# Microcontroller.net
KiCad netlist of a schematic drawn in Altium Designer
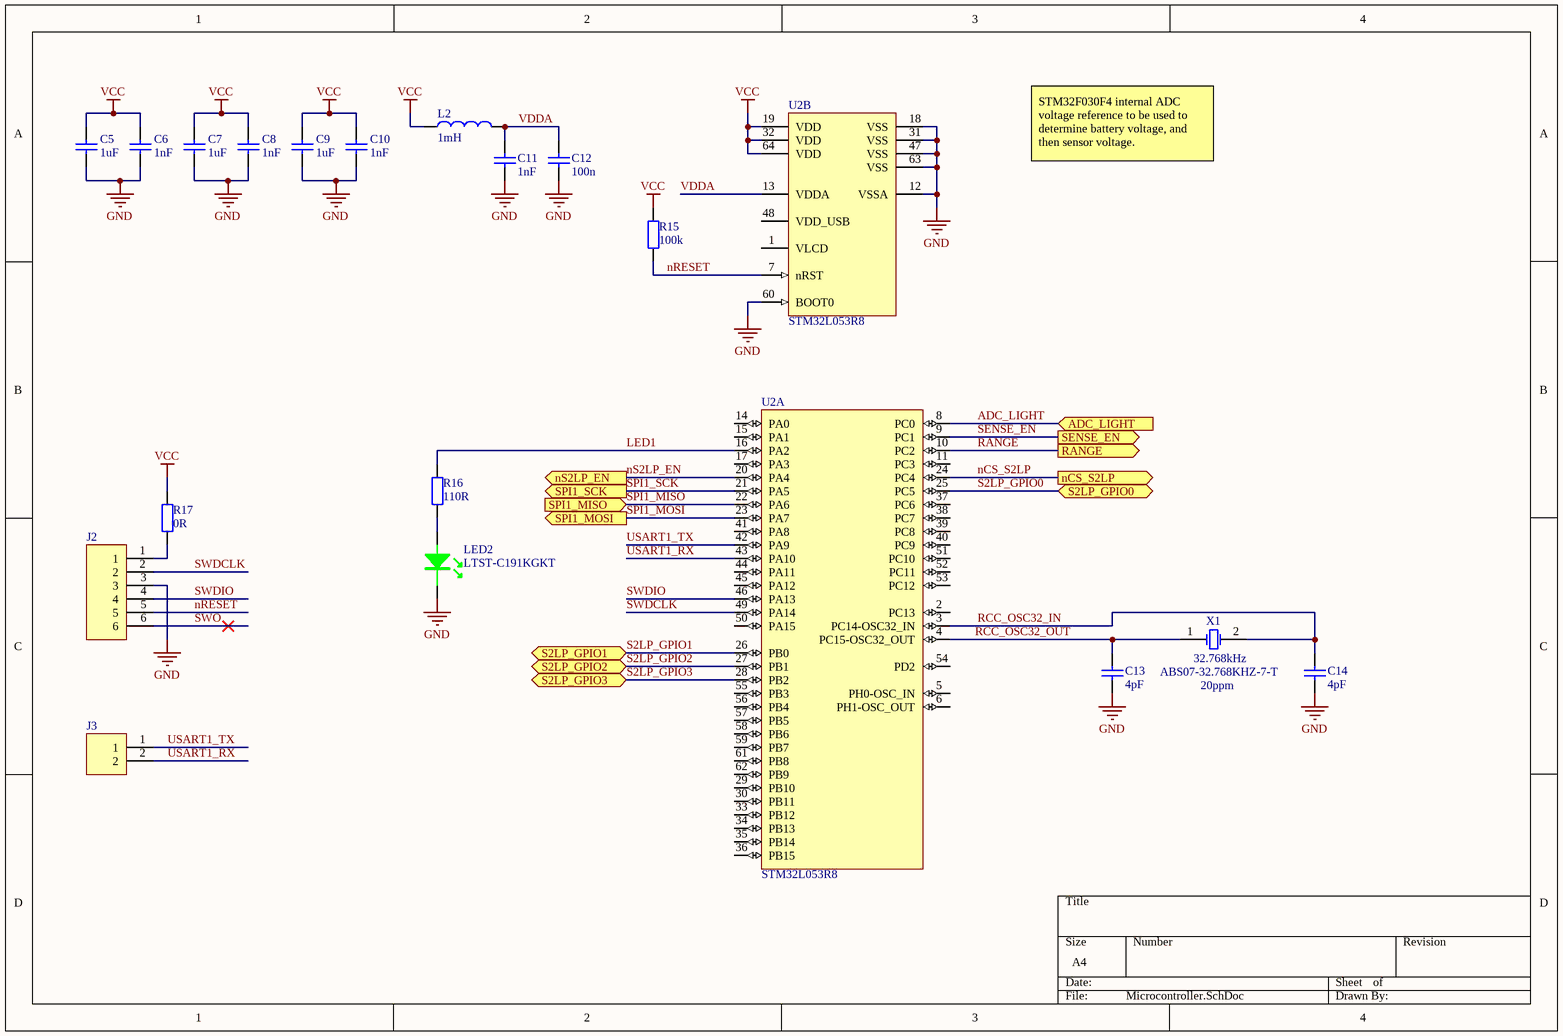
[diagram p0: Microcontroller.SchDoc]

(export (version "E")
  (design (tool "Eeschema 10.0.6"))
  (components
    (comp (ref "C5")
      (value "~")
      (footprint "C0603")
      (description "CAP")
      (fields
        (field (name "MANUFACTURER") "Yageo")
        (field (name "MANUFACTURER PART NUMBER") "CC0603KRX7R9BB105")
        (field (name "CAPACITANCE") "1uF")
      )
      (libsource (lib "Light Sensor Node") (part "CAP"))
    )
    (comp (ref "C6")
      (value "1nF")
      (footprint "C0603")
      (description "CAP")
      (fields
        (field (name "MANUFACTURER") "Yageo")
        (field (name "MANUFACTURER PART NUMBER") "CC0603KRX7R9BB102")
      )
      (libsource (lib "Light Sensor Node") (part "CAP"))
    )
    (comp (ref "C7")
      (value "~")
      (footprint "C0603")
      (description "CAP")
      (fields
        (field (name "MANUFACTURER") "Yageo")
        (field (name "MANUFACTURER PART NUMBER") "CC0603KRX7R9BB105")
        (field (name "CAPACITANCE") "1uF")
      )
      (libsource (lib "Light Sensor Node") (part "CAP"))
    )
    (comp (ref "C8")
      (value "1nF")
      (footprint "C0603")
      (description "CAP")
      (fields
        (field (name "MANUFACTURER") "Yageo")
        (field (name "MANUFACTURER PART NUMBER") "CC0603KRX7R9BB102")
      )
      (libsource (lib "Light Sensor Node") (part "CAP"))
    )
    (comp (ref "C9")
      (value "~")
      (footprint "C0603")
      (description "CAP")
      (fields
        (field (name "MANUFACTURER") "Yageo")
        (field (name "MANUFACTURER PART NUMBER") "CC0603KRX7R9BB105")
        (field (name "CAPACITANCE") "1uF")
      )
      (libsource (lib "Light Sensor Node") (part "CAP"))
    )
    (comp (ref "C10")
      (value "1nF")
      (footprint "C0603")
      (description "CAP")
      (fields
        (field (name "MANUFACTURER") "Yageo")
        (field (name "MANUFACTURER PART NUMBER") "CC0603KRX7R9BB102")
      )
      (libsource (lib "Light Sensor Node") (part "CAP"))
    )
    (comp (ref "C11")
      (value "1nF")
      (footprint "C0603")
      (description "CAP")
      (fields
        (field (name "MANUFACTURER") "Yageo")
        (field (name "MANUFACTURER PART NUMBER") "CC0603KRX7R9BB102")
      )
      (libsource (lib "Light Sensor Node") (part "CAP"))
    )
    (comp (ref "C12")
      (value "100n")
      (footprint "C0603")
      (description "CAP")
      (fields
        (field (name "MANUFACTURER") "Yageo")
        (field (name "MANUFACTURER PART NUMBER") "CC0603ZRY5V9BB104")
      )
      (libsource (lib "Light Sensor Node") (part "CAP"))
    )
    (comp (ref "C13")
      (value "4pF")
      (footprint "C0603")
      (description "CAP")
      (fields
        (field (name "MANUFACTURER") "Yageo")
        (field (name "MANUFACTURER PART NUMBER") "CC0603CRNPO9BN4R0")
      )
      (libsource (lib "Light Sensor Node") (part "CAP"))
    )
    (comp (ref "C14")
      (value "4pF")
      (footprint "C0603")
      (description "CAP")
      (fields
        (field (name "MANUFACTURER") "Yageo")
        (field (name "MANUFACTURER PART NUMBER") "CC0603CRNPO9BN4R0")
      )
      (libsource (lib "Light Sensor Node") (part "CAP"))
    )
    (comp (ref "J2")
      (value "~")
      (footprint "HEADER_6WAY")
      (libsource (lib "Light Sensor Node") (part "6WAY"))
    )
    (comp (ref "J3")
      (value "~")
      (footprint "HEADER_2WAY")
      (libsource (lib "Light Sensor Node") (part "2WAY"))
    )
    (comp (ref "L2")
      (value "IND")
      (footprint "TAIYOYUDEN_CB2518T102K")
      (fields
        (field (name "MANUFACTURER") "Taiyo Yuden")
        (field (name "MANUFACTURER PART NUMBER") "CB2518T102K")
        (field (name "INDUCTANCE") "1mH")
      )
      (libsource (lib "Light Sensor Node") (part "IND"))
    )
    (comp (ref "LED2")
      (value "LTST-C191KGKT")
      (footprint "LITEON_LTST-C191KGKT")
      (fields (field (name "MANUFACTURER") "Lite On"))
      (libsource (lib "Light Sensor Node") (part "LED_Green"))
    )
    (comp (ref "R15")
      (value "100k")
      (footprint "R0603")
      (description "RES")
      (fields (field (name "TOLERANCE") "1%") (field (name "MANUFACTURER") "Yageo"))
      (libsource (lib "") (part "RES_1"))
    )
    (comp (ref "R16")
      (value "110R")
      (footprint "R0603")
      (description "RES")
      (fields
        (field (name "MANUFACTURER") "Yageo")
        (field (name "MANUFACTURER PART NUMBER") "RC0603FR-07110RL")
      )
      (libsource (lib "") (part "RES_1"))
    )
    (comp (ref "R17")
      (value "0R")
      (footprint "R0603")
      (description "RES")
      (fields
        (field (name "MANUFACTURER") "Yageo")
        (field (name "MANUFACTURER PART NUMBER") "RC0603JR-070RL")
      )
      (libsource (lib "Light Sensor Node") (part "RES"))
    )
    (comp (ref "U2")
      (value "STM32L053R8")
      (footprint "ST_STM32L053R8Tx")
      (fields (field (name "MANUFACTURER") "ST"))
      (libsource (lib "Light Sensor Node") (part "STM32L053R8"))
    )
    (comp (ref "X1")
      (value "32.768kHz")
      (footprint "Abracon_ABS07")
      (description "Crystal Oscillator")
      (fields
        (field (name "MANUFACTURER") "Abracon")
        (field (name "MANUFACTURER PART NUMBER") "ABS07-32.768KHZ-7-T")
        (field (name "FREQUENCY TOLERANCE") "20ppm")
      )
      (libsource (lib "Light Sensor Node") (part "ABRACON_ABS07"))
    )
  )
  (nets
    (net (code "1") (name "/ADC_LIGHT") (class "Default")
      (node (ref "U2") (pin "8") (pinfunction "PC0_8") (pintype "bidirectional"))
    )
    (net (code "2") (name "/LED1") (class "Default")
      (node (ref "R16") (pin "1") (pinfunction "1_1") (pintype "passive"))
      (node (ref "U2") (pin "16") (pinfunction "PA2_16") (pintype "bidirectional"))
    )
    (net (code "3") (name "/RANGE") (class "Default")
      (node (ref "U2") (pin "10") (pinfunction "PC2_10") (pintype "bidirectional"))
    )
    (net (code "4") (name "/RCC_OSC32_IN") (class "Default")
      (node (ref "C14") (pin "2") (pinfunction "2_2") (pintype "passive"))
      (node (ref "U2") (pin "3") (pinfunction "PC14-OSC32_IN_3") (pintype "bidirectional"))
      (node (ref "X1") (pin "2") (pinfunction "OSC2_2") (pintype "passive"))
    )
    (net (code "5") (name "/RCC_OSC32_OUT") (class "Default")
      (node (ref "C13") (pin "2") (pinfunction "2_2") (pintype "passive"))
      (node (ref "U2") (pin "4") (pinfunction "PC15-OSC32_OUT_4") (pintype "bidirectional"))
      (node (ref "X1") (pin "1") (pinfunction "OSC1_1") (pintype "passive"))
    )
    (net (code "6") (name "/S2LP_GPIO0") (class "Default")
      (node (ref "U2") (pin "25") (pinfunction "PC5_25") (pintype "bidirectional"))
    )
    (net (code "7") (name "/S2LP_GPIO1") (class "Default")
      (node (ref "U2") (pin "26") (pinfunction "PB0_26") (pintype "bidirectional"))
    )
    (net (code "8") (name "/S2LP_GPIO2") (class "Default")
      (node (ref "U2") (pin "27") (pinfunction "PB1_27") (pintype "bidirectional"))
    )
    (net (code "9") (name "/S2LP_GPIO3") (class "Default")
      (node (ref "U2") (pin "28") (pinfunction "PB2_28") (pintype "bidirectional"))
    )
    (net (code "10") (name "/SENSE_EN") (class "Default")
      (node (ref "U2") (pin "9") (pinfunction "PC1_9") (pintype "bidirectional"))
    )
    (net (code "11") (name "/SPI1_MISO") (class "Default")
      (node (ref "U2") (pin "22") (pinfunction "PA6_22") (pintype "bidirectional"))
    )
    (net (code "12") (name "/SPI1_MOSI") (class "Default")
      (node (ref "U2") (pin "23") (pinfunction "PA7_23") (pintype "bidirectional"))
    )
    (net (code "13") (name "/SPI1_SCK") (class "Default")
      (node (ref "U2") (pin "21") (pinfunction "PA5_21") (pintype "bidirectional"))
    )
    (net (code "14") (name "/SWDCLK") (class "Default")
      (node (ref "J2") (pin "2") (pinfunction "2_2") (pintype "passive"))
      (node (ref "U2") (pin "49") (pinfunction "PA14_49") (pintype "bidirectional"))
    )
    (net (code "15") (name "/SWDIO") (class "Default")
      (node (ref "J2") (pin "4") (pinfunction "4_4") (pintype "passive"))
      (node (ref "U2") (pin "46") (pinfunction "PA13_46") (pintype "bidirectional"))
    )
    (net (code "16") (name "/SWO") (class "Default")
      (node (ref "J2") (pin "6") (pinfunction "6_6") (pintype "passive"))
    )
    (net (code "17") (name "/USART1_RX") (class "Default")
      (node (ref "J3") (pin "2") (pinfunction "2_2") (pintype "passive"))
      (node (ref "U2") (pin "43") (pinfunction "PA10_43") (pintype "bidirectional"))
    )
    (net (code "18") (name "/USART1_TX") (class "Default")
      (node (ref "J3") (pin "1") (pinfunction "1_1") (pintype "passive"))
      (node (ref "U2") (pin "42") (pinfunction "PA9_42") (pintype "bidirectional"))
    )
    (net (code "19") (name "/VDDA") (class "Default")
      (node (ref "C11") (pin "1") (pinfunction "1_1") (pintype "passive"))
      (node (ref "C12") (pin "2") (pinfunction "2_2") (pintype "passive"))
      (node (ref "L2") (pin "1") (pinfunction "1_1") (pintype "passive"))
      (node (ref "U2") (pin "13") (pinfunction "VDDA_13") (pintype "power_in"))
    )
    (net (code "20") (name "/nCS_S2LP") (class "Default")
      (node (ref "U2") (pin "24") (pinfunction "PC4_24") (pintype "bidirectional"))
    )
    (net (code "21") (name "/nRESET") (class "Default")
      (node (ref "J2") (pin "5") (pinfunction "5_5") (pintype "passive"))
      (node (ref "R15") (pin "2") (pinfunction "2_2") (pintype "passive"))
      (node (ref "U2") (pin "7") (pinfunction "nRST_7") (pintype "input"))
    )
    (net (code "22") (name "/nS2LP_EN") (class "Default")
      (node (ref "U2") (pin "20") (pinfunction "PA4_20") (pintype "bidirectional"))
    )
    (net (code "23") (name "GND") (class "Default")
      (node (ref "C10") (pin "2") (pinfunction "2_2") (pintype "passive"))
      (node (ref "C11") (pin "2") (pinfunction "2_2") (pintype "passive"))
      (node (ref "C12") (pin "1") (pinfunction "1_1") (pintype "passive"))
      (node (ref "C13") (pin "1") (pinfunction "1_1") (pintype "passive"))
      (node (ref "C14") (pin "1") (pinfunction "1_1") (pintype "passive"))
      (node (ref "C5") (pin "1") (pinfunction "1_1") (pintype "passive"))
      (node (ref "C6") (pin "2") (pinfunction "2_2") (pintype "passive"))
      (node (ref "C7") (pin "1") (pinfunction "1_1") (pintype "passive"))
      (node (ref "C8") (pin "2") (pinfunction "2_2") (pintype "passive"))
      (node (ref "C9") (pin "1") (pinfunction "1_1") (pintype "passive"))
      (node (ref "J2") (pin "3") (pinfunction "3_3") (pintype "passive"))
      (node (ref "LED2") (pin "K") (pinfunction "K_K") (pintype "passive"))
      (node (ref "U2") (pin "12") (pinfunction "VSSA_12") (pintype "power_in"))
      (node (ref "U2") (pin "18") (pinfunction "VSS_18") (pintype "power_in"))
      (node (ref "U2") (pin "31") (pinfunction "VSS_31") (pintype "power_in"))
      (node (ref "U2") (pin "47") (pinfunction "VSS_47") (pintype "power_in"))
      (node (ref "U2") (pin "60") (pinfunction "BOOT0_60") (pintype "input"))
      (node (ref "U2") (pin "63") (pinfunction "VSS_63") (pintype "power_in"))
    )
    (net (code "24") (name "Net-(J2-Pad1)") (class "Default")
      (node (ref "J2") (pin "1") (pinfunction "1_1") (pintype "passive"))
      (node (ref "R17") (pin "1") (pinfunction "1_1") (pintype "passive"))
    )
    (net (code "25") (name "Net-(LED2-PadA)") (class "Default")
      (node (ref "LED2") (pin "A") (pinfunction "A_A") (pintype "passive"))
      (node (ref "R16") (pin "2") (pinfunction "2_2") (pintype "passive"))
    )
    (net (code "26") (name "VCC") (class "Default")
      (node (ref "C10") (pin "1") (pinfunction "1_1") (pintype "passive"))
      (node (ref "C5") (pin "2") (pinfunction "2_2") (pintype "passive"))
      (node (ref "C6") (pin "1") (pinfunction "1_1") (pintype "passive"))
      (node (ref "C7") (pin "2") (pinfunction "2_2") (pintype "passive"))
      (node (ref "C8") (pin "1") (pinfunction "1_1") (pintype "passive"))
      (node (ref "C9") (pin "2") (pinfunction "2_2") (pintype "passive"))
      (node (ref "L2") (pin "2") (pinfunction "2_2") (pintype "passive"))
      (node (ref "R15") (pin "1") (pinfunction "1_1") (pintype "passive"))
      (node (ref "R17") (pin "2") (pinfunction "2_2") (pintype "passive"))
      (node (ref "U2") (pin "19") (pinfunction "VDD_19") (pintype "power_in"))
      (node (ref "U2") (pin "32") (pinfunction "VDD_32") (pintype "power_in"))
      (node (ref "U2") (pin "64") (pinfunction "VDD_64") (pintype "power_in"))
    )
    (net (code "27") (name "unconnected-(U2A-PA0-Pad14)") (class "Default")
      (node (ref "U2") (pin "14") (pinfunction "PA0_14") (pintype "bidirectional"))
    )
    (net (code "28") (name "unconnected-(U2A-PA1-Pad15)") (class "Default")
      (node (ref "U2") (pin "15") (pinfunction "PA1_15") (pintype "bidirectional"))
    )
    (net (code "29") (name "unconnected-(U2A-PA3-Pad17)") (class "Default")
      (node (ref "U2") (pin "17") (pinfunction "PA3_17") (pintype "bidirectional"))
    )
    (net (code "30") (name "unconnected-(U2A-PA8-Pad41)") (class "Default")
      (node (ref "U2") (pin "41") (pinfunction "PA8_41") (pintype "bidirectional"))
    )
    (net (code "31") (name "unconnected-(U2A-PA11-Pad44)") (class "Default")
      (node (ref "U2") (pin "44") (pinfunction "PA11_44") (pintype "bidirectional"))
    )
    (net (code "32") (name "unconnected-(U2A-PA12-Pad45)") (class "Default")
      (node (ref "U2") (pin "45") (pinfunction "PA12_45") (pintype "bidirectional"))
    )
    (net (code "33") (name "unconnected-(U2A-PA15-Pad50)") (class "Default")
      (node (ref "U2") (pin "50") (pinfunction "PA15_50") (pintype "bidirectional"))
    )
    (net (code "34") (name "unconnected-(U2A-PB3-Pad55)") (class "Default")
      (node (ref "U2") (pin "55") (pinfunction "PB3_55") (pintype "bidirectional"))
    )
    (net (code "35") (name "unconnected-(U2A-PB4-Pad56)") (class "Default")
      (node (ref "U2") (pin "56") (pinfunction "PB4_56") (pintype "bidirectional"))
    )
    (net (code "36") (name "unconnected-(U2A-PB5-Pad57)") (class "Default")
      (node (ref "U2") (pin "57") (pinfunction "PB5_57") (pintype "bidirectional"))
    )
    (net (code "37") (name "unconnected-(U2A-PB6-Pad58)") (class "Default")
      (node (ref "U2") (pin "58") (pinfunction "PB6_58") (pintype "bidirectional"))
    )
    (net (code "38") (name "unconnected-(U2A-PB7-Pad59)") (class "Default")
      (node (ref "U2") (pin "59") (pinfunction "PB7_59") (pintype "bidirectional"))
    )
    (net (code "39") (name "unconnected-(U2A-PB8-Pad61)") (class "Default")
      (node (ref "U2") (pin "61") (pinfunction "PB8_61") (pintype "bidirectional"))
    )
    (net (code "40") (name "unconnected-(U2A-PB9-Pad62)") (class "Default")
      (node (ref "U2") (pin "62") (pinfunction "PB9_62") (pintype "bidirectional"))
    )
    (net (code "41") (name "unconnected-(U2A-PB10-Pad29)") (class "Default")
      (node (ref "U2") (pin "29") (pinfunction "PB10_29") (pintype "bidirectional"))
    )
    (net (code "42") (name "unconnected-(U2A-PB11-Pad30)") (class "Default")
      (node (ref "U2") (pin "30") (pinfunction "PB11_30") (pintype "bidirectional"))
    )
    (net (code "43") (name "unconnected-(U2A-PB12-Pad33)") (class "Default")
      (node (ref "U2") (pin "33") (pinfunction "PB12_33") (pintype "bidirectional"))
    )
    (net (code "44") (name "unconnected-(U2A-PB13-Pad34)") (class "Default")
      (node (ref "U2") (pin "34") (pinfunction "PB13_34") (pintype "bidirectional"))
    )
    (net (code "45") (name "unconnected-(U2A-PB14-Pad35)") (class "Default")
      (node (ref "U2") (pin "35") (pinfunction "PB14_35") (pintype "bidirectional"))
    )
    (net (code "46") (name "unconnected-(U2A-PB15-Pad36)") (class "Default")
      (node (ref "U2") (pin "36") (pinfunction "PB15_36") (pintype "bidirectional"))
    )
    (net (code "47") (name "unconnected-(U2A-PC3-Pad11)") (class "Default")
      (node (ref "U2") (pin "11") (pinfunction "PC3_11") (pintype "bidirectional"))
    )
    (net (code "48") (name "unconnected-(U2A-PC6-Pad37)") (class "Default")
      (node (ref "U2") (pin "37") (pinfunction "PC6_37") (pintype "bidirectional"))
    )
    (net (code "49") (name "unconnected-(U2A-PC7-Pad38)") (class "Default")
      (node (ref "U2") (pin "38") (pinfunction "PC7_38") (pintype "bidirectional"))
    )
    (net (code "50") (name "unconnected-(U2A-PC8-Pad39)") (class "Default")
      (node (ref "U2") (pin "39") (pinfunction "PC8_39") (pintype "bidirectional"))
    )
    (net (code "51") (name "unconnected-(U2A-PC9-Pad40)") (class "Default")
      (node (ref "U2") (pin "40") (pinfunction "PC9_40") (pintype "bidirectional"))
    )
    (net (code "52") (name "unconnected-(U2A-PC10-Pad51)") (class "Default")
      (node (ref "U2") (pin "51") (pinfunction "PC10_51") (pintype "bidirectional"))
    )
    (net (code "53") (name "unconnected-(U2A-PC11-Pad52)") (class "Default")
      (node (ref "U2") (pin "52") (pinfunction "PC11_52") (pintype "bidirectional"))
    )
    (net (code "54") (name "unconnected-(U2A-PC12-Pad53)") (class "Default")
      (node (ref "U2") (pin "53") (pinfunction "PC12_53") (pintype "bidirectional"))
    )
    (net (code "55") (name "unconnected-(U2A-PC13-Pad2)") (class "Default")
      (node (ref "U2") (pin "2") (pinfunction "PC13_2") (pintype "bidirectional"))
    )
    (net (code "56") (name "unconnected-(U2A-PD2-Pad54)") (class "Default")
      (node (ref "U2") (pin "54") (pinfunction "PD2_54") (pintype "bidirectional"))
    )
    (net (code "57") (name "unconnected-(U2A-PH0-OSC_IN-Pad5)") (class "Default")
      (node (ref "U2") (pin "5") (pinfunction "PH0-OSC_IN_5") (pintype "bidirectional"))
    )
    (net (code "58") (name "unconnected-(U2A-PH1-OSC_OUT-Pad6)") (class "Default")
      (node (ref "U2") (pin "6") (pinfunction "PH1-OSC_OUT_6") (pintype "bidirectional"))
    )
    (net (code "59") (name "unconnected-(U2B-VDD_USB-Pad48)") (class "Default")
      (node (ref "U2") (pin "48") (pinfunction "VDD_USB_48") (pintype "power_in"))
    )
    (net (code "60") (name "unconnected-(U2B-VLCD-Pad1)") (class "Default")
      (node (ref "U2") (pin "1") (pinfunction "VLCD_1") (pintype "power_in"))
    )
  )
)
